# GRRVboardCGROUP2015.net
KiCad netlist of a schematic drawn in EAGLE
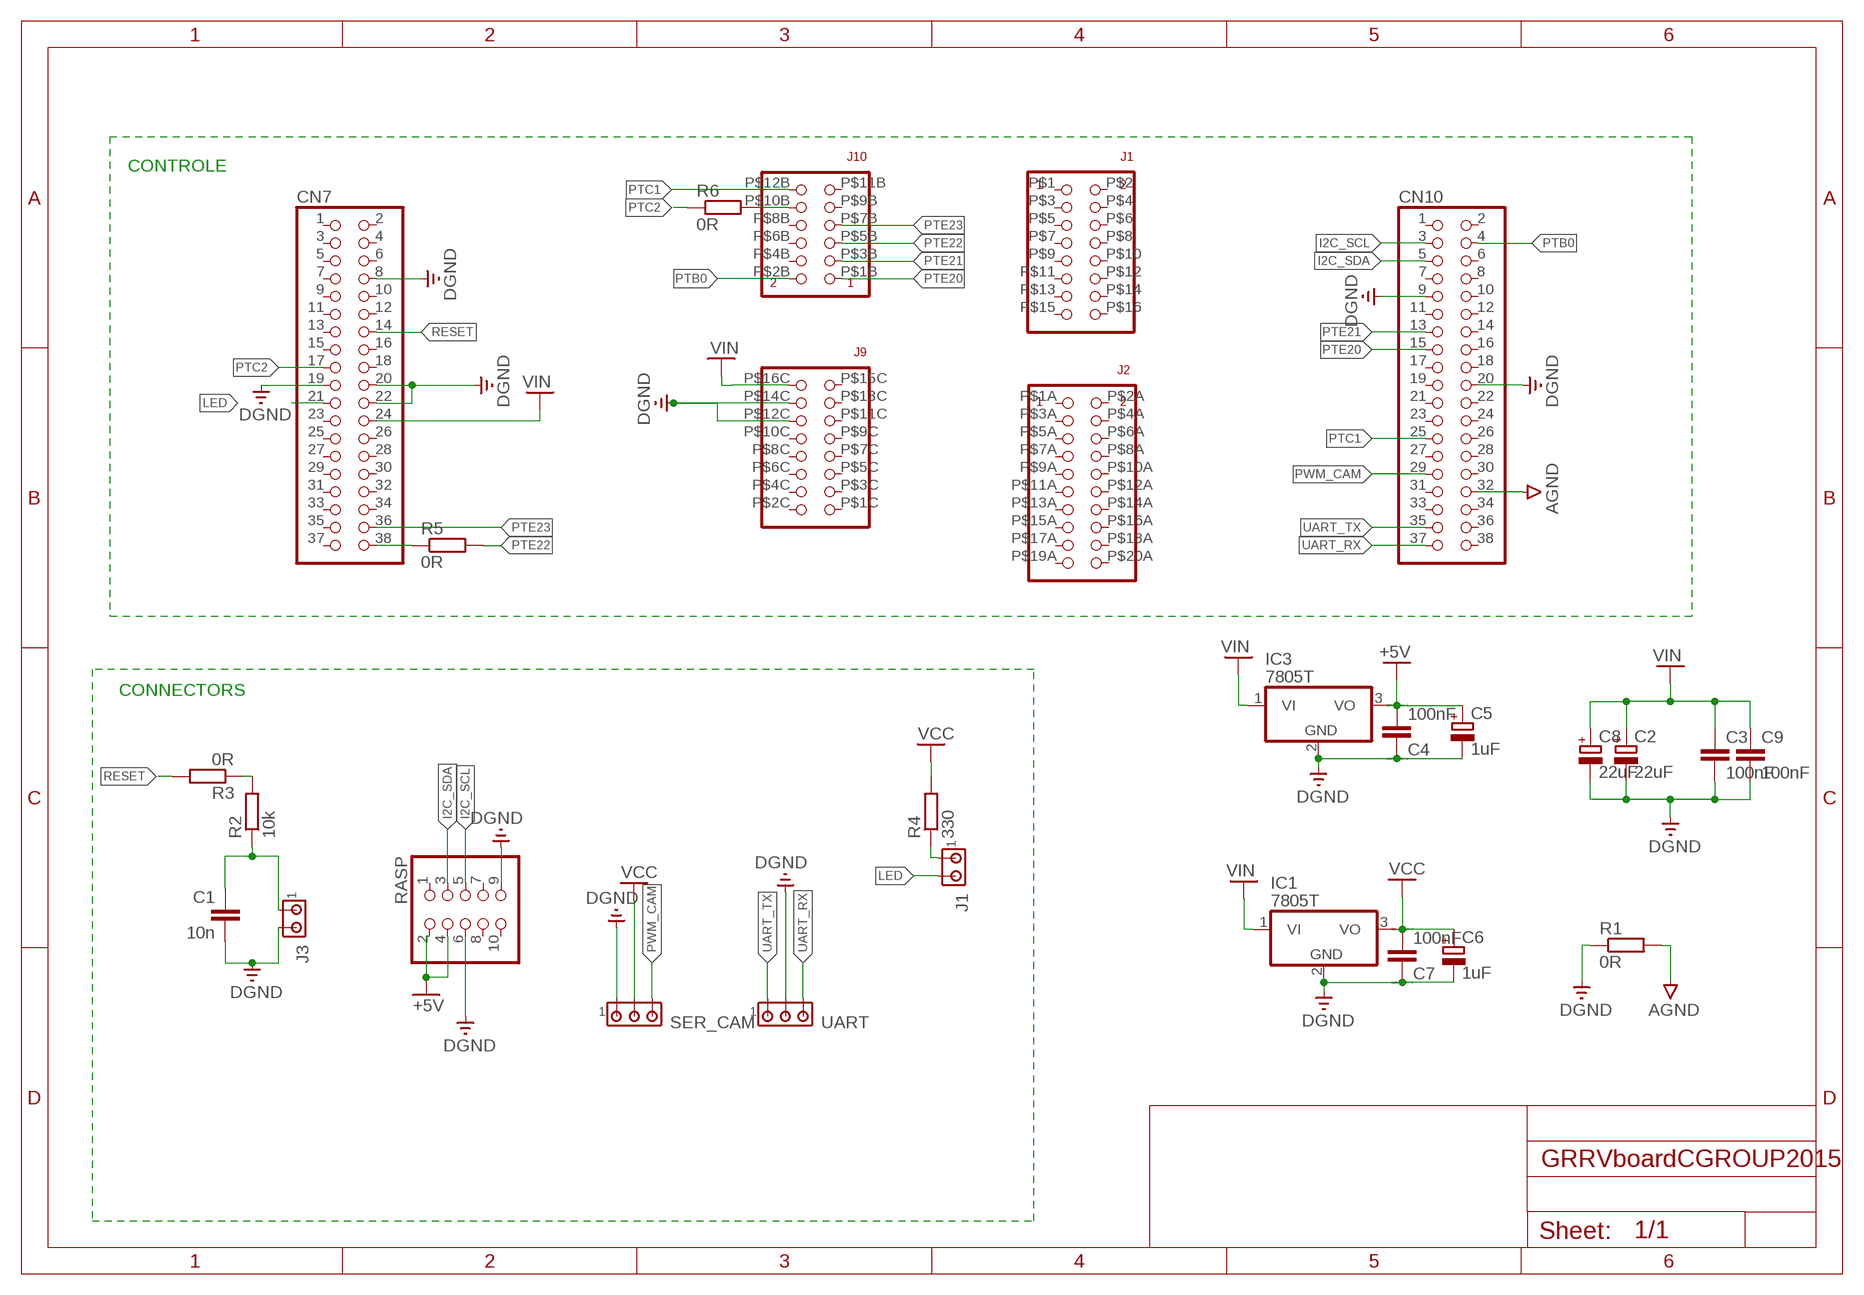
[diagram p0: schematic, sheet 1]

(export (version "E")
  (design (tool "Eeschema 10.0.6"))
  (components
    (comp (ref "C1")
      (value "10n")
      (footprint "eagle-import:C0805")
      (libsource (lib "eagle-import") (part "C-EUC0805"))
    )
    (comp (ref "C2")
      (value "22uF")
      (footprint "eagle-import:SMC_B")
      (libsource (lib "eagle-import") (part "CPOL-EUSMCB"))
    )
    (comp (ref "C3")
      (value "100nF")
      (footprint "eagle-import:C0805")
      (libsource (lib "eagle-import") (part "C-EUC0805"))
    )
    (comp (ref "C4")
      (value "100nF")
      (footprint "eagle-import:C0805")
      (libsource (lib "eagle-import") (part "C"))
    )
    (comp (ref "C5")
      (value "1uF")
      (footprint "eagle-import:SMC_B")
      (libsource (lib "eagle-import") (part "CPOL-EUSMCB"))
    )
    (comp (ref "C6")
      (value "1uF")
      (footprint "eagle-import:SMC_B")
      (libsource (lib "eagle-import") (part "CPOL-EUSMCB"))
    )
    (comp (ref "C7")
      (value "100nF")
      (footprint "eagle-import:C0805")
      (libsource (lib "eagle-import") (part "C"))
    )
    (comp (ref "C8")
      (value "22uF")
      (footprint "eagle-import:SMC_B")
      (libsource (lib "eagle-import") (part "CPOL-EUSMCB"))
    )
    (comp (ref "C9")
      (value "100nF")
      (footprint "eagle-import:C0805")
      (libsource (lib "eagle-import") (part "C-EUC0805"))
    )
    (comp (ref "CN7")
      (value "PINHD-2X19")
      (footprint "eagle-import:2X19")
      (libsource (lib "eagle-import") (part "PINHD-2X19"))
    )
    (comp (ref "CN10")
      (value "PINHD-2X19")
      (footprint "eagle-import:2X19")
      (libsource (lib "eagle-import") (part "PINHD-2X19"))
    )
    (comp (ref "IC1")
      (value "7805T")
      (footprint "eagle-import:TO220H")
      (libsource (lib "eagle-import") (part "78T05"))
    )
    (comp (ref "IC3")
      (value "7805T")
      (footprint "eagle-import:TO220H")
      (libsource (lib "eagle-import") (part "78T05"))
    )
    (comp (ref "J1")
      (value "MTA02-100")
      (footprint "eagle-import:10X02MTA")
      (libsource (lib "eagle-import") (part "MTA02-100"))
    )
    (comp (ref "J3")
      (value "MTA02-100")
      (footprint "eagle-import:10X02MTA")
      (libsource (lib "eagle-import") (part "MTA02-100"))
    )
    (comp (ref "R1")
      (value "0R")
      (footprint "eagle-import:M1206")
      (libsource (lib "eagle-import") (part "resistor_R-EU_M1206"))
    )
    (comp (ref "R2")
      (value "10k")
      (footprint "eagle-import:M0805")
      (libsource (lib "eagle-import") (part "resistor_R-EU_M0805"))
    )
    (comp (ref "R3")
      (value "0R")
      (footprint "eagle-import:R0805")
      (libsource (lib "eagle-import") (part "R-EU_R0805"))
    )
    (comp (ref "R4")
      (value "330")
      (footprint "eagle-import:M0805")
      (libsource (lib "eagle-import") (part "resistor_R-EU_M0805"))
    )
    (comp (ref "R5")
      (value "0R")
      (footprint "eagle-import:R0805")
      (libsource (lib "eagle-import") (part "R-EU_R0805"))
    )
    (comp (ref "R6")
      (value "0R")
      (footprint "eagle-import:R0805")
      (libsource (lib "eagle-import") (part "R-EU_R0805"))
    )
    (comp (ref "RASP")
      (value "PINHD-2X5")
      (footprint "eagle-import:2X05")
      (libsource (lib "eagle-import") (part "PINHD-2X5"))
    )
    (comp (ref "SER_CAM")
      (value "MTA03-100")
      (footprint "eagle-import:10X03MTA")
      (libsource (lib "eagle-import") (part "MTA03-100"))
    )
    (comp (ref "U$1")
      (value "FRDM-TFC")
      (footprint "eagle-import:FRDM")
      (libsource (lib "eagle-import") (part "FRDM-TFC"))
    )
    (comp (ref "UART")
      (value "MTA03-100")
      (footprint "eagle-import:10X03MTA")
      (libsource (lib "eagle-import") (part "MTA03-100"))
    )
  )
  (nets
    (net (code "1") (name "+5V") (class "Default")
      (node (ref "C4") (pin "2") (pinfunction "2_2") (pintype "passive"))
      (node (ref "C5") (pin "+") (pinfunction "+_+") (pintype "passive"))
      (node (ref "IC3") (pin "3") (pinfunction "VO_3") (pintype "passive"))
      (node (ref "RASP") (pin "2") (pinfunction "2_2") (pintype "passive"))
      (node (ref "RASP") (pin "4") (pinfunction "4_4") (pintype "passive"))
    )
    (net (code "2") (name "AGND") (class "Default")
      (node (ref "CN10") (pin "32") (pinfunction "32_32") (pintype "passive"))
      (node (ref "R1") (pin "2") (pinfunction "2_2") (pintype "passive"))
    )
    (net (code "3") (name "DGND") (class "Default")
      (node (ref "C1") (pin "2") (pinfunction "2_2") (pintype "passive"))
      (node (ref "C2") (pin "-") (pinfunction "-_-") (pintype "passive"))
      (node (ref "C3") (pin "2") (pinfunction "2_2") (pintype "passive"))
      (node (ref "C4") (pin "1") (pinfunction "1_1") (pintype "passive"))
      (node (ref "C5") (pin "-") (pinfunction "-_-") (pintype "passive"))
      (node (ref "C6") (pin "-") (pinfunction "-_-") (pintype "passive"))
      (node (ref "C7") (pin "1") (pinfunction "1_1") (pintype "passive"))
      (node (ref "C8") (pin "-") (pinfunction "-_-") (pintype "passive"))
      (node (ref "C9") (pin "2") (pinfunction "2_2") (pintype "passive"))
      (node (ref "CN10") (pin "20") (pinfunction "20_20") (pintype "passive"))
      (node (ref "CN10") (pin "9") (pinfunction "9_9") (pintype "passive"))
      (node (ref "CN7") (pin "19") (pinfunction "19_19") (pintype "passive"))
      (node (ref "CN7") (pin "20") (pinfunction "20_20") (pintype "passive"))
      (node (ref "CN7") (pin "22") (pinfunction "22_22") (pintype "passive"))
      (node (ref "CN7") (pin "8") (pinfunction "8_8") (pintype "passive"))
      (node (ref "IC1") (pin "2") (pinfunction "GND_2") (pintype "passive"))
      (node (ref "IC3") (pin "2") (pinfunction "GND_2") (pintype "passive"))
      (node (ref "J3") (pin "2") (pinfunction "2_2") (pintype "passive"))
      (node (ref "R1") (pin "1") (pinfunction "1_1") (pintype "passive"))
      (node (ref "RASP") (pin "6") (pinfunction "6_6") (pintype "passive"))
      (node (ref "RASP") (pin "9") (pinfunction "9_9") (pintype "passive"))
      (node (ref "SER_CAM") (pin "1") (pinfunction "1_1") (pintype "passive"))
      (node (ref "U$1") (pin "P$12C") (pinfunction "12C_P$12C") (pintype "passive"))
      (node (ref "U$1") (pin "P$14C") (pinfunction "14C_P$14C") (pintype "passive"))
      (node (ref "UART") (pin "2") (pinfunction "2_2") (pintype "passive"))
    )
    (net (code "4") (name "I2C_SCL") (class "Default")
      (node (ref "CN10") (pin "3") (pinfunction "3_3") (pintype "passive"))
      (node (ref "RASP") (pin "5") (pinfunction "5_5") (pintype "passive"))
    )
    (net (code "5") (name "I2C_SDA") (class "Default")
      (node (ref "CN10") (pin "5") (pinfunction "5_5") (pintype "passive"))
      (node (ref "RASP") (pin "3") (pinfunction "3_3") (pintype "passive"))
    )
    (net (code "6") (name "LED") (class "Default")
      (node (ref "CN7") (pin "21") (pinfunction "21_21") (pintype "passive"))
      (node (ref "J1") (pin "2") (pinfunction "2_2") (pintype "passive"))
    )
    (net (code "7") (name "Net-(C1-Pad1)") (class "Default")
      (node (ref "C1") (pin "1") (pinfunction "1_1") (pintype "passive"))
      (node (ref "J3") (pin "1") (pinfunction "1_1") (pintype "passive"))
      (node (ref "R2") (pin "1") (pinfunction "1_1") (pintype "passive"))
    )
    (net (code "8") (name "Net-(CN7-Pad38)") (class "Default")
      (node (ref "CN7") (pin "38") (pinfunction "38_38") (pintype "passive"))
      (node (ref "R5") (pin "1") (pinfunction "1_1") (pintype "passive"))
    )
    (net (code "9") (name "Net-(J1-Pad1)") (class "Default")
      (node (ref "J1") (pin "1") (pinfunction "1_1") (pintype "passive"))
      (node (ref "R4") (pin "1") (pinfunction "1_1") (pintype "passive"))
    )
    (net (code "10") (name "Net-(R2-Pad2)") (class "Default")
      (node (ref "R2") (pin "2") (pinfunction "2_2") (pintype "passive"))
      (node (ref "R3") (pin "1") (pinfunction "1_1") (pintype "passive"))
    )
    (net (code "11") (name "Net-(U$1-10B)") (class "Default")
      (node (ref "R6") (pin "2") (pinfunction "2_2") (pintype "passive"))
      (node (ref "U$1") (pin "P$10B") (pinfunction "10B_P$10B") (pintype "passive"))
    )
    (net (code "12") (name "PTB0") (class "Default")
      (node (ref "CN10") (pin "4") (pinfunction "4_4") (pintype "passive"))
      (node (ref "U$1") (pin "P$2B") (pinfunction "2B_P$2B") (pintype "passive"))
    )
    (net (code "13") (name "PTC1") (class "Default")
      (node (ref "CN10") (pin "25") (pinfunction "25_25") (pintype "passive"))
      (node (ref "U$1") (pin "P$12B") (pinfunction "12B_P$12B") (pintype "passive"))
    )
    (net (code "14") (name "PTC2") (class "Default")
      (node (ref "CN7") (pin "17") (pinfunction "17_17") (pintype "passive"))
      (node (ref "R6") (pin "1") (pinfunction "1_1") (pintype "passive"))
    )
    (net (code "15") (name "PTE20") (class "Default")
      (node (ref "CN10") (pin "15") (pinfunction "15_15") (pintype "passive"))
      (node (ref "U$1") (pin "P$1B") (pinfunction "1B_P$1B") (pintype "passive"))
    )
    (net (code "16") (name "PTE21") (class "Default")
      (node (ref "CN10") (pin "13") (pinfunction "13_13") (pintype "passive"))
      (node (ref "U$1") (pin "P$3B") (pinfunction "3B_P$3B") (pintype "passive"))
    )
    (net (code "17") (name "PTE22") (class "Default")
      (node (ref "R5") (pin "2") (pinfunction "2_2") (pintype "passive"))
      (node (ref "U$1") (pin "P$5B") (pinfunction "5B_P$5B") (pintype "passive"))
    )
    (net (code "18") (name "PTE23") (class "Default")
      (node (ref "CN7") (pin "36") (pinfunction "36_36") (pintype "passive"))
      (node (ref "U$1") (pin "P$7B") (pinfunction "7B_P$7B") (pintype "passive"))
    )
    (net (code "19") (name "PWM_CAM") (class "Default")
      (node (ref "CN10") (pin "29") (pinfunction "29_29") (pintype "passive"))
      (node (ref "SER_CAM") (pin "3") (pinfunction "3_3") (pintype "passive"))
    )
    (net (code "20") (name "RESET") (class "Default")
      (node (ref "CN7") (pin "14") (pinfunction "14_14") (pintype "passive"))
      (node (ref "R3") (pin "2") (pinfunction "2_2") (pintype "passive"))
    )
    (net (code "21") (name "UART_RX") (class "Default")
      (node (ref "CN10") (pin "37") (pinfunction "37_37") (pintype "passive"))
      (node (ref "UART") (pin "3") (pinfunction "3_3") (pintype "passive"))
    )
    (net (code "22") (name "UART_TX") (class "Default")
      (node (ref "CN10") (pin "35") (pinfunction "35_35") (pintype "passive"))
      (node (ref "UART") (pin "1") (pinfunction "1_1") (pintype "passive"))
    )
    (net (code "23") (name "VCC") (class "Default")
      (node (ref "C6") (pin "+") (pinfunction "+_+") (pintype "passive"))
      (node (ref "C7") (pin "2") (pinfunction "2_2") (pintype "passive"))
      (node (ref "IC1") (pin "3") (pinfunction "VO_3") (pintype "passive"))
      (node (ref "R4") (pin "2") (pinfunction "2_2") (pintype "passive"))
      (node (ref "SER_CAM") (pin "2") (pinfunction "2_2") (pintype "passive"))
    )
    (net (code "24") (name "VIN") (class "Default")
      (node (ref "C2") (pin "+") (pinfunction "+_+") (pintype "passive"))
      (node (ref "C3") (pin "1") (pinfunction "1_1") (pintype "passive"))
      (node (ref "C8") (pin "+") (pinfunction "+_+") (pintype "passive"))
      (node (ref "C9") (pin "1") (pinfunction "1_1") (pintype "passive"))
      (node (ref "CN7") (pin "24") (pinfunction "24_24") (pintype "passive"))
      (node (ref "IC1") (pin "1") (pinfunction "VI_1") (pintype "input"))
      (node (ref "IC3") (pin "1") (pinfunction "VI_1") (pintype "input"))
      (node (ref "U$1") (pin "P$16C") (pinfunction "16C_P$16C") (pintype "passive"))
    )
    (net (code "25") (name "unconnected-(CN7-Pad1)") (class "Default")
      (node (ref "CN7") (pin "1") (pinfunction "1_1") (pintype "passive"))
    )
    (net (code "26") (name "unconnected-(CN7-Pad2)") (class "Default")
      (node (ref "CN7") (pin "2") (pinfunction "2_2") (pintype "passive"))
    )
    (net (code "27") (name "unconnected-(CN7-Pad3)") (class "Default")
      (node (ref "CN7") (pin "3") (pinfunction "3_3") (pintype "passive"))
    )
    (net (code "28") (name "unconnected-(CN7-Pad4)") (class "Default")
      (node (ref "CN7") (pin "4") (pinfunction "4_4") (pintype "passive"))
    )
    (net (code "29") (name "unconnected-(CN7-Pad5)") (class "Default")
      (node (ref "CN7") (pin "5") (pinfunction "5_5") (pintype "passive"))
    )
    (net (code "30") (name "unconnected-(CN7-Pad6)") (class "Default")
      (node (ref "CN7") (pin "6") (pinfunction "6_6") (pintype "passive"))
    )
    (net (code "31") (name "unconnected-(CN7-Pad7)") (class "Default")
      (node (ref "CN7") (pin "7") (pinfunction "7_7") (pintype "passive"))
    )
    (net (code "32") (name "unconnected-(CN7-Pad9)") (class "Default")
      (node (ref "CN7") (pin "9") (pinfunction "9_9") (pintype "passive"))
    )
    (net (code "33") (name "unconnected-(CN7-Pad10)") (class "Default")
      (node (ref "CN7") (pin "10") (pinfunction "10_10") (pintype "passive"))
    )
    (net (code "34") (name "unconnected-(CN7-Pad11)") (class "Default")
      (node (ref "CN7") (pin "11") (pinfunction "11_11") (pintype "passive"))
    )
    (net (code "35") (name "unconnected-(CN7-Pad12)") (class "Default")
      (node (ref "CN7") (pin "12") (pinfunction "12_12") (pintype "passive"))
    )
    (net (code "36") (name "unconnected-(CN7-Pad13)") (class "Default")
      (node (ref "CN7") (pin "13") (pinfunction "13_13") (pintype "passive"))
    )
    (net (code "37") (name "unconnected-(CN7-Pad15)") (class "Default")
      (node (ref "CN7") (pin "15") (pinfunction "15_15") (pintype "passive"))
    )
    (net (code "38") (name "unconnected-(CN7-Pad16)") (class "Default")
      (node (ref "CN7") (pin "16") (pinfunction "16_16") (pintype "passive"))
    )
    (net (code "39") (name "unconnected-(CN7-Pad18)") (class "Default")
      (node (ref "CN7") (pin "18") (pinfunction "18_18") (pintype "passive"))
    )
    (net (code "40") (name "unconnected-(CN7-Pad23)") (class "Default")
      (node (ref "CN7") (pin "23") (pinfunction "23_23") (pintype "passive"))
    )
    (net (code "41") (name "unconnected-(CN7-Pad25)") (class "Default")
      (node (ref "CN7") (pin "25") (pinfunction "25_25") (pintype "passive"))
    )
    (net (code "42") (name "unconnected-(CN7-Pad26)") (class "Default")
      (node (ref "CN7") (pin "26") (pinfunction "26_26") (pintype "passive"))
    )
    (net (code "43") (name "unconnected-(CN7-Pad27)") (class "Default")
      (node (ref "CN7") (pin "27") (pinfunction "27_27") (pintype "passive"))
    )
    (net (code "44") (name "unconnected-(CN7-Pad28)") (class "Default")
      (node (ref "CN7") (pin "28") (pinfunction "28_28") (pintype "passive"))
    )
    (net (code "45") (name "unconnected-(CN7-Pad29)") (class "Default")
      (node (ref "CN7") (pin "29") (pinfunction "29_29") (pintype "passive"))
    )
    (net (code "46") (name "unconnected-(CN7-Pad30)") (class "Default")
      (node (ref "CN7") (pin "30") (pinfunction "30_30") (pintype "passive"))
    )
    (net (code "47") (name "unconnected-(CN7-Pad31)") (class "Default")
      (node (ref "CN7") (pin "31") (pinfunction "31_31") (pintype "passive"))
    )
    (net (code "48") (name "unconnected-(CN7-Pad32)") (class "Default")
      (node (ref "CN7") (pin "32") (pinfunction "32_32") (pintype "passive"))
    )
    (net (code "49") (name "unconnected-(CN7-Pad33)") (class "Default")
      (node (ref "CN7") (pin "33") (pinfunction "33_33") (pintype "passive"))
    )
    (net (code "50") (name "unconnected-(CN7-Pad34)") (class "Default")
      (node (ref "CN7") (pin "34") (pinfunction "34_34") (pintype "passive"))
    )
    (net (code "51") (name "unconnected-(CN7-Pad35)") (class "Default")
      (node (ref "CN7") (pin "35") (pinfunction "35_35") (pintype "passive"))
    )
    (net (code "52") (name "unconnected-(CN7-Pad37)") (class "Default")
      (node (ref "CN7") (pin "37") (pinfunction "37_37") (pintype "passive"))
    )
    (net (code "53") (name "unconnected-(CN10-Pad1)") (class "Default")
      (node (ref "CN10") (pin "1") (pinfunction "1_1") (pintype "passive"))
    )
    (net (code "54") (name "unconnected-(CN10-Pad2)") (class "Default")
      (node (ref "CN10") (pin "2") (pinfunction "2_2") (pintype "passive"))
    )
    (net (code "55") (name "unconnected-(CN10-Pad6)") (class "Default")
      (node (ref "CN10") (pin "6") (pinfunction "6_6") (pintype "passive"))
    )
    (net (code "56") (name "unconnected-(CN10-Pad7)") (class "Default")
      (node (ref "CN10") (pin "7") (pinfunction "7_7") (pintype "passive"))
    )
    (net (code "57") (name "unconnected-(CN10-Pad8)") (class "Default")
      (node (ref "CN10") (pin "8") (pinfunction "8_8") (pintype "passive"))
    )
    (net (code "58") (name "unconnected-(CN10-Pad10)") (class "Default")
      (node (ref "CN10") (pin "10") (pinfunction "10_10") (pintype "passive"))
    )
    (net (code "59") (name "unconnected-(CN10-Pad11)") (class "Default")
      (node (ref "CN10") (pin "11") (pinfunction "11_11") (pintype "passive"))
    )
    (net (code "60") (name "unconnected-(CN10-Pad12)") (class "Default")
      (node (ref "CN10") (pin "12") (pinfunction "12_12") (pintype "passive"))
    )
    (net (code "61") (name "unconnected-(CN10-Pad14)") (class "Default")
      (node (ref "CN10") (pin "14") (pinfunction "14_14") (pintype "passive"))
    )
    (net (code "62") (name "unconnected-(CN10-Pad16)") (class "Default")
      (node (ref "CN10") (pin "16") (pinfunction "16_16") (pintype "passive"))
    )
    (net (code "63") (name "unconnected-(CN10-Pad17)") (class "Default")
      (node (ref "CN10") (pin "17") (pinfunction "17_17") (pintype "passive"))
    )
    (net (code "64") (name "unconnected-(CN10-Pad18)") (class "Default")
      (node (ref "CN10") (pin "18") (pinfunction "18_18") (pintype "passive"))
    )
    (net (code "65") (name "unconnected-(CN10-Pad19)") (class "Default")
      (node (ref "CN10") (pin "19") (pinfunction "19_19") (pintype "passive"))
    )
    (net (code "66") (name "unconnected-(CN10-Pad21)") (class "Default")
      (node (ref "CN10") (pin "21") (pinfunction "21_21") (pintype "passive"))
    )
    (net (code "67") (name "unconnected-(CN10-Pad22)") (class "Default")
      (node (ref "CN10") (pin "22") (pinfunction "22_22") (pintype "passive"))
    )
    (net (code "68") (name "unconnected-(CN10-Pad23)") (class "Default")
      (node (ref "CN10") (pin "23") (pinfunction "23_23") (pintype "passive"))
    )
    (net (code "69") (name "unconnected-(CN10-Pad24)") (class "Default")
      (node (ref "CN10") (pin "24") (pinfunction "24_24") (pintype "passive"))
    )
    (net (code "70") (name "unconnected-(CN10-Pad26)") (class "Default")
      (node (ref "CN10") (pin "26") (pinfunction "26_26") (pintype "passive"))
    )
    (net (code "71") (name "unconnected-(CN10-Pad27)") (class "Default")
      (node (ref "CN10") (pin "27") (pinfunction "27_27") (pintype "passive"))
    )
    (net (code "72") (name "unconnected-(CN10-Pad28)") (class "Default")
      (node (ref "CN10") (pin "28") (pinfunction "28_28") (pintype "passive"))
    )
    (net (code "73") (name "unconnected-(CN10-Pad30)") (class "Default")
      (node (ref "CN10") (pin "30") (pinfunction "30_30") (pintype "passive"))
    )
    (net (code "74") (name "unconnected-(CN10-Pad31)") (class "Default")
      (node (ref "CN10") (pin "31") (pinfunction "31_31") (pintype "passive"))
    )
    (net (code "75") (name "unconnected-(CN10-Pad33)") (class "Default")
      (node (ref "CN10") (pin "33") (pinfunction "33_33") (pintype "passive"))
    )
    (net (code "76") (name "unconnected-(CN10-Pad34)") (class "Default")
      (node (ref "CN10") (pin "34") (pinfunction "34_34") (pintype "passive"))
    )
    (net (code "77") (name "unconnected-(CN10-Pad36)") (class "Default")
      (node (ref "CN10") (pin "36") (pinfunction "36_36") (pintype "passive"))
    )
    (net (code "78") (name "unconnected-(CN10-Pad38)") (class "Default")
      (node (ref "CN10") (pin "38") (pinfunction "38_38") (pintype "passive"))
    )
    (net (code "79") (name "unconnected-(RASP-Pad1)") (class "Default")
      (node (ref "RASP") (pin "1") (pinfunction "1_1") (pintype "passive"))
    )
    (net (code "80") (name "unconnected-(RASP-Pad7)") (class "Default")
      (node (ref "RASP") (pin "7") (pinfunction "7_7") (pintype "passive"))
    )
    (net (code "81") (name "unconnected-(RASP-Pad8)") (class "Default")
      (node (ref "RASP") (pin "8") (pinfunction "8_8") (pintype "passive"))
    )
    (net (code "82") (name "unconnected-(RASP-Pad10)") (class "Default")
      (node (ref "RASP") (pin "10") (pinfunction "10_10") (pintype "passive"))
    )
    (net (code "83") (name "unconnected-(U$1-1-PadP$1)") (class "Default")
      (node (ref "U$1") (pin "P$1") (pinfunction "1_P$1") (pintype "passive"))
    )
    (net (code "84") (name "unconnected-(U$1-1A-PadP$1A)") (class "Default")
      (node (ref "U$1") (pin "P$1A") (pinfunction "1A_P$1A") (pintype "passive"))
    )
    (net (code "85") (name "unconnected-(U$1-1C-PadP$1C)") (class "Default")
      (node (ref "U$1") (pin "P$1C") (pinfunction "1C_P$1C") (pintype "passive"))
    )
    (net (code "86") (name "unconnected-(U$1-2-PadP$2)") (class "Default")
      (node (ref "U$1") (pin "P$2") (pinfunction "2_P$2") (pintype "passive"))
    )
    (net (code "87") (name "unconnected-(U$1-2A-PadP$2A)") (class "Default")
      (node (ref "U$1") (pin "P$2A") (pinfunction "2A_P$2A") (pintype "passive"))
    )
    (net (code "88") (name "unconnected-(U$1-2C-PadP$2C)") (class "Default")
      (node (ref "U$1") (pin "P$2C") (pinfunction "2C_P$2C") (pintype "passive"))
    )
    (net (code "89") (name "unconnected-(U$1-3-PadP$3)") (class "Default")
      (node (ref "U$1") (pin "P$3") (pinfunction "3_P$3") (pintype "passive"))
    )
    (net (code "90") (name "unconnected-(U$1-3A-PadP$3A)") (class "Default")
      (node (ref "U$1") (pin "P$3A") (pinfunction "3A_P$3A") (pintype "passive"))
    )
    (net (code "91") (name "unconnected-(U$1-3C-PadP$3C)") (class "Default")
      (node (ref "U$1") (pin "P$3C") (pinfunction "3C_P$3C") (pintype "passive"))
    )
    (net (code "92") (name "unconnected-(U$1-4-PadP$4)") (class "Default")
      (node (ref "U$1") (pin "P$4") (pinfunction "4_P$4") (pintype "passive"))
    )
    (net (code "93") (name "unconnected-(U$1-4A-PadP$4A)") (class "Default")
      (node (ref "U$1") (pin "P$4A") (pinfunction "4A_P$4A") (pintype "passive"))
    )
    (net (code "94") (name "unconnected-(U$1-4B-PadP$4B)") (class "Default")
      (node (ref "U$1") (pin "P$4B") (pinfunction "4B_P$4B") (pintype "passive"))
    )
    (net (code "95") (name "unconnected-(U$1-4C-PadP$4C)") (class "Default")
      (node (ref "U$1") (pin "P$4C") (pinfunction "4C_P$4C") (pintype "passive"))
    )
    (net (code "96") (name "unconnected-(U$1-5-PadP$5)") (class "Default")
      (node (ref "U$1") (pin "P$5") (pinfunction "5_P$5") (pintype "passive"))
    )
    (net (code "97") (name "unconnected-(U$1-5A-PadP$5A)") (class "Default")
      (node (ref "U$1") (pin "P$5A") (pinfunction "5A_P$5A") (pintype "passive"))
    )
    (net (code "98") (name "unconnected-(U$1-5C-PadP$5C)") (class "Default")
      (node (ref "U$1") (pin "P$5C") (pinfunction "5C_P$5C") (pintype "passive"))
    )
    (net (code "99") (name "unconnected-(U$1-6-PadP$6)") (class "Default")
      (node (ref "U$1") (pin "P$6") (pinfunction "6_P$6") (pintype "passive"))
    )
    (net (code "100") (name "unconnected-(U$1-6A-PadP$6A)") (class "Default")
      (node (ref "U$1") (pin "P$6A") (pinfunction "6A_P$6A") (pintype "passive"))
    )
    (net (code "101") (name "unconnected-(U$1-6B-PadP$6B)") (class "Default")
      (node (ref "U$1") (pin "P$6B") (pinfunction "6B_P$6B") (pintype "passive"))
    )
    (net (code "102") (name "unconnected-(U$1-6C-PadP$6C)") (class "Default")
      (node (ref "U$1") (pin "P$6C") (pinfunction "6C_P$6C") (pintype "passive"))
    )
    (net (code "103") (name "unconnected-(U$1-7-PadP$7)") (class "Default")
      (node (ref "U$1") (pin "P$7") (pinfunction "7_P$7") (pintype "passive"))
    )
    (net (code "104") (name "unconnected-(U$1-7A-PadP$7A)") (class "Default")
      (node (ref "U$1") (pin "P$7A") (pinfunction "7A_P$7A") (pintype "passive"))
    )
    (net (code "105") (name "unconnected-(U$1-7C-PadP$7C)") (class "Default")
      (node (ref "U$1") (pin "P$7C") (pinfunction "7C_P$7C") (pintype "passive"))
    )
    (net (code "106") (name "unconnected-(U$1-8-PadP$8)") (class "Default")
      (node (ref "U$1") (pin "P$8") (pinfunction "8_P$8") (pintype "passive"))
    )
    (net (code "107") (name "unconnected-(U$1-8A-PadP$8A)") (class "Default")
      (node (ref "U$1") (pin "P$8A") (pinfunction "8A_P$8A") (pintype "passive"))
    )
    (net (code "108") (name "unconnected-(U$1-8B-PadP$8B)") (class "Default")
      (node (ref "U$1") (pin "P$8B") (pinfunction "8B_P$8B") (pintype "passive"))
    )
    (net (code "109") (name "unconnected-(U$1-8C-PadP$8C)") (class "Default")
      (node (ref "U$1") (pin "P$8C") (pinfunction "8C_P$8C") (pintype "passive"))
    )
    (net (code "110") (name "unconnected-(U$1-9-PadP$9)") (class "Default")
      (node (ref "U$1") (pin "P$9") (pinfunction "9_P$9") (pintype "passive"))
    )
    (net (code "111") (name "unconnected-(U$1-9A-PadP$9A)") (class "Default")
      (node (ref "U$1") (pin "P$9A") (pinfunction "9A_P$9A") (pintype "passive"))
    )
    (net (code "112") (name "unconnected-(U$1-9B-PadP$9B)") (class "Default")
      (node (ref "U$1") (pin "P$9B") (pinfunction "9B_P$9B") (pintype "passive"))
    )
    (net (code "113") (name "unconnected-(U$1-9C-PadP$9C)") (class "Default")
      (node (ref "U$1") (pin "P$9C") (pinfunction "9C_P$9C") (pintype "passive"))
    )
    (net (code "114") (name "unconnected-(U$1-10-PadP$10)") (class "Default")
      (node (ref "U$1") (pin "P$10") (pinfunction "10_P$10") (pintype "passive"))
    )
    (net (code "115") (name "unconnected-(U$1-10A-PadP$10A)") (class "Default")
      (node (ref "U$1") (pin "P$10A") (pinfunction "10A_P$10A") (pintype "passive"))
    )
    (net (code "116") (name "unconnected-(U$1-10C-PadP$10C)") (class "Default")
      (node (ref "U$1") (pin "P$10C") (pinfunction "10C_P$10C") (pintype "passive"))
    )
    (net (code "117") (name "unconnected-(U$1-11-PadP$11)") (class "Default")
      (node (ref "U$1") (pin "P$11") (pinfunction "11_P$11") (pintype "passive"))
    )
    (net (code "118") (name "unconnected-(U$1-11A-PadP$11A)") (class "Default")
      (node (ref "U$1") (pin "P$11A") (pinfunction "11A_P$11A") (pintype "passive"))
    )
    (net (code "119") (name "unconnected-(U$1-11B-PadP$11B)") (class "Default")
      (node (ref "U$1") (pin "P$11B") (pinfunction "11B_P$11B") (pintype "passive"))
    )
    (net (code "120") (name "unconnected-(U$1-11C-PadP$11C)") (class "Default")
      (node (ref "U$1") (pin "P$11C") (pinfunction "11C_P$11C") (pintype "passive"))
    )
    (net (code "121") (name "unconnected-(U$1-12-PadP$12)") (class "Default")
      (node (ref "U$1") (pin "P$12") (pinfunction "12_P$12") (pintype "passive"))
    )
    (net (code "122") (name "unconnected-(U$1-12A-PadP$12A)") (class "Default")
      (node (ref "U$1") (pin "P$12A") (pinfunction "12A_P$12A") (pintype "passive"))
    )
    (net (code "123") (name "unconnected-(U$1-13-PadP$13)") (class "Default")
      (node (ref "U$1") (pin "P$13") (pinfunction "13_P$13") (pintype "passive"))
    )
    (net (code "124") (name "unconnected-(U$1-13A-PadP$13A)") (class "Default")
      (node (ref "U$1") (pin "P$13A") (pinfunction "13A_P$13A") (pintype "passive"))
    )
    (net (code "125") (name "unconnected-(U$1-13C-PadP$13C)") (class "Default")
      (node (ref "U$1") (pin "P$13C") (pinfunction "13C_P$13C") (pintype "passive"))
    )
    (net (code "126") (name "unconnected-(U$1-14-PadP$14)") (class "Default")
      (node (ref "U$1") (pin "P$14") (pinfunction "14_P$14") (pintype "passive"))
    )
    (net (code "127") (name "unconnected-(U$1-14A-PadP$14A)") (class "Default")
      (node (ref "U$1") (pin "P$14A") (pinfunction "14A_P$14A") (pintype "passive"))
    )
    (net (code "128") (name "unconnected-(U$1-15-PadP$15)") (class "Default")
      (node (ref "U$1") (pin "P$15") (pinfunction "15_P$15") (pintype "passive"))
    )
    (net (code "129") (name "unconnected-(U$1-15A-PadP$15A)") (class "Default")
      (node (ref "U$1") (pin "P$15A") (pinfunction "15A_P$15A") (pintype "passive"))
    )
    (net (code "130") (name "unconnected-(U$1-15C-PadP$15C)") (class "Default")
      (node (ref "U$1") (pin "P$15C") (pinfunction "15C_P$15C") (pintype "passive"))
    )
    (net (code "131") (name "unconnected-(U$1-16-PadP$16)") (class "Default")
      (node (ref "U$1") (pin "P$16") (pinfunction "16_P$16") (pintype "passive"))
    )
    (net (code "132") (name "unconnected-(U$1-16A-PadP$16A)") (class "Default")
      (node (ref "U$1") (pin "P$16A") (pinfunction "16A_P$16A") (pintype "passive"))
    )
    (net (code "133") (name "unconnected-(U$1-17A-PadP$17A)") (class "Default")
      (node (ref "U$1") (pin "P$17A") (pinfunction "17A_P$17A") (pintype "passive"))
    )
    (net (code "134") (name "unconnected-(U$1-18A-PadP$18A)") (class "Default")
      (node (ref "U$1") (pin "P$18A") (pinfunction "18A_P$18A") (pintype "passive"))
    )
    (net (code "135") (name "unconnected-(U$1-19A-PadP$19A)") (class "Default")
      (node (ref "U$1") (pin "P$19A") (pinfunction "19A_P$19A") (pintype "passive"))
    )
    (net (code "136") (name "unconnected-(U$1-20A-PadP$20A)") (class "Default")
      (node (ref "U$1") (pin "P$20A") (pinfunction "20A_P$20A") (pintype "passive"))
    )
  )
)
